# 06_NRF24L01.net
KiCad netlist of a schematic drawn in Altium Designer
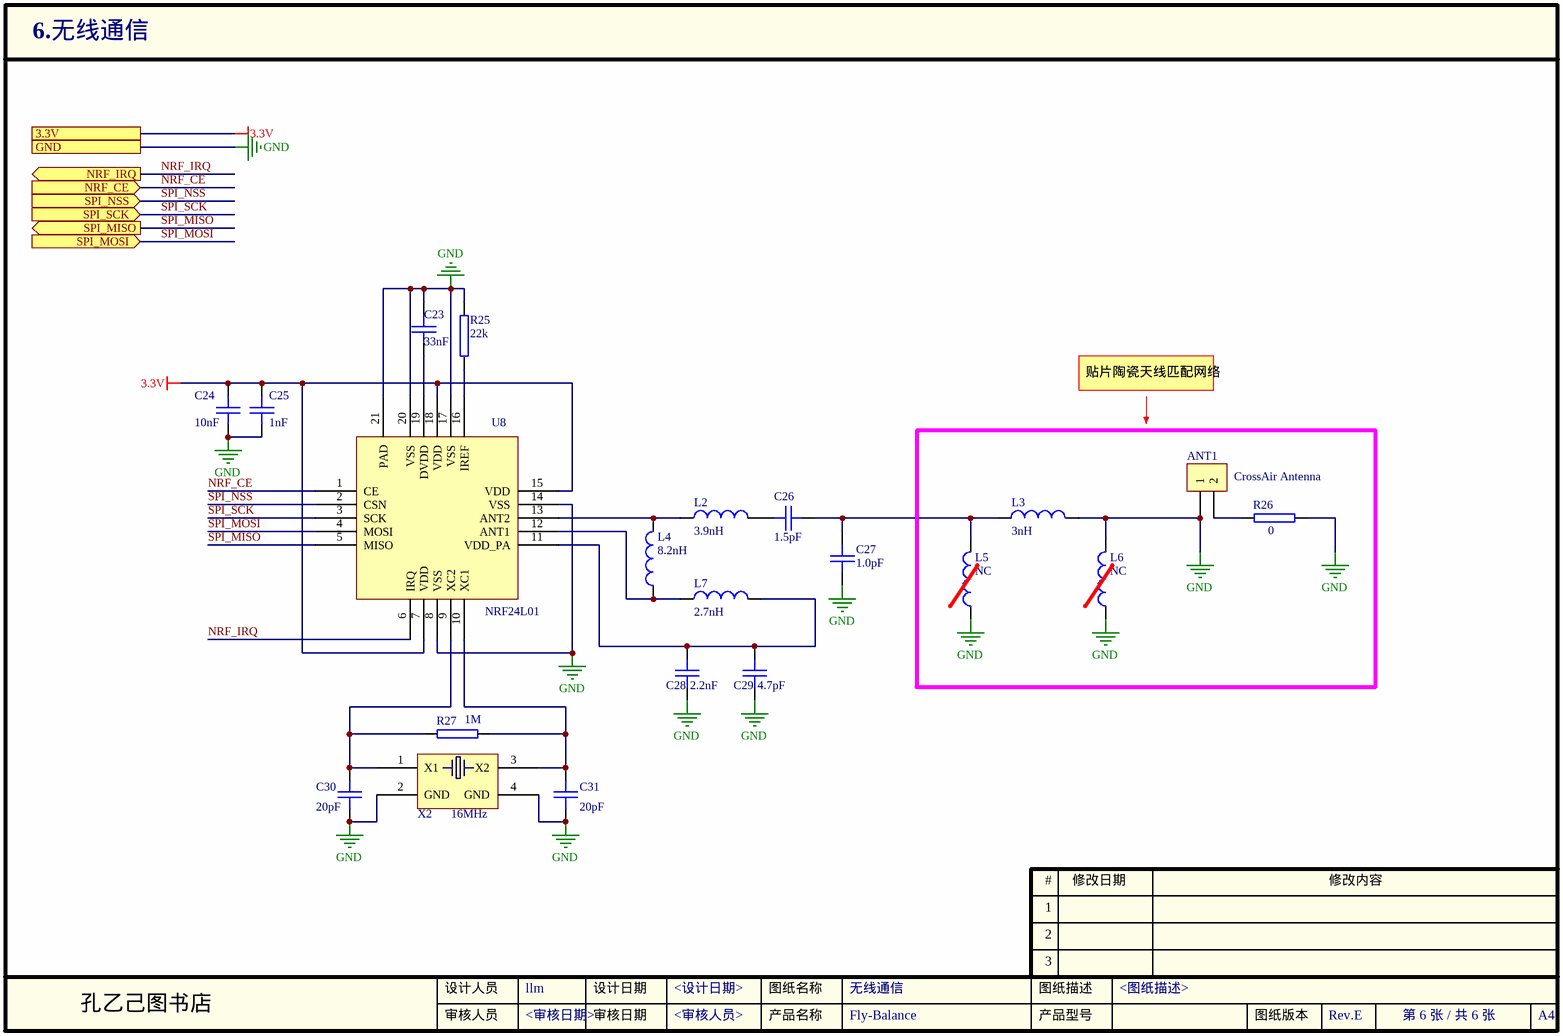
[diagram p0: 06_NRF24L01.SchDoc]

(export (version "E")
  (design (tool "Eeschema 10.0.6"))
  (components
    (comp (ref "ANT1")
      (value "CrossAir Antenna")
      (footprint "ANT-SMD_L3.1-W1.6")
      (description "Connector")
      (libsource (lib "MY_Schlib") (part "CON2"))
    )
    (comp (ref "C23")
      (value "33nF")
      (footprint "0402C")
      (description "电容")
      (libsource (lib "MY_Schlib") (part "CAP"))
    )
    (comp (ref "C24")
      (value "10nF")
      (footprint "0402C")
      (description "电容")
      (libsource (lib "MY_Schlib") (part "CAP"))
    )
    (comp (ref "C25")
      (value "1nF")
      (footprint "0402C")
      (description "电容")
      (libsource (lib "MY_Schlib") (part "CAP"))
    )
    (comp (ref "C26")
      (value "1.5pF")
      (footprint "0402C")
      (description "电容")
      (libsource (lib "MY_Schlib") (part "CAP"))
    )
    (comp (ref "C27")
      (value "1.0pF")
      (footprint "0402C")
      (description "电容")
      (libsource (lib "MY_Schlib") (part "CAP"))
    )
    (comp (ref "C28")
      (value "2.2nF")
      (footprint "0402C")
      (description "电容")
      (libsource (lib "MY_Schlib") (part "CAP"))
    )
    (comp (ref "C29")
      (value "4.7pF")
      (footprint "0402C")
      (description "电容")
      (libsource (lib "MY_Schlib") (part "CAP"))
    )
    (comp (ref "C30")
      (value "20pF")
      (footprint "0402C")
      (description "电容")
      (libsource (lib "MY_Schlib") (part "CAP"))
    )
    (comp (ref "C31")
      (value "20pF")
      (footprint "0402C")
      (description "电容")
      (libsource (lib "MY_Schlib") (part "CAP"))
    )
    (comp (ref "L2")
      (value "3.9nH")
      (footprint "0402R")
      (description "电感")
      (libsource (lib "") (part "INDUCTOR_1_1"))
    )
    (comp (ref "L3")
      (value "3nH")
      (footprint "0402R")
      (description "电感")
      (libsource (lib "") (part "INDUCTOR_1_1"))
    )
    (comp (ref "L4")
      (value "8.2nH")
      (footprint "0402R")
      (description "电感")
      (libsource (lib "MY_Schlib") (part "INDUCTOR_1"))
    )
    (comp (ref "L5")
      (value "NC")
      (footprint "0402R")
      (description "电感")
      (libsource (lib "MY_Schlib") (part "INDUCTOR_1"))
    )
    (comp (ref "L6")
      (value "NC")
      (footprint "0402R")
      (description "电感")
      (libsource (lib "MY_Schlib") (part "INDUCTOR_1"))
    )
    (comp (ref "L7")
      (value "2.7nH")
      (footprint "0402R")
      (description "电感")
      (libsource (lib "") (part "INDUCTOR_1_1"))
    )
    (comp (ref "R25")
      (value "22k")
      (footprint "0402R")
      (description "电阻")
      (libsource (lib "MY_Schlib") (part "RES"))
    )
    (comp (ref "R26")
      (value "0")
      (footprint "0402R")
      (description "电阻")
      (libsource (lib "MY_Schlib") (part "RES"))
    )
    (comp (ref "R27")
      (value "1M")
      (footprint "0402R")
      (description "电阻")
      (libsource (lib "MY_Schlib") (part "RES"))
    )
    (comp (ref "U8")
      (value "NRF24L01")
      (footprint "QFN-20_L4.0-W4.0-P0.50-BL-EP")
      (description "2.4G无线通信芯片")
      (libsource (lib "MY_Schlib") (part "NRF24L01"))
    )
    (comp (ref "X2")
      (value "16MHz")
      (footprint "OSCCC250X320X80-4N")
      (description "4pin贴片无源晶振")
      (libsource (lib "MY_Schlib") (part "XTAL4"))
    )
  )
  (nets
    (net (code "1") (name "/NRF_CE") (class "Default")
      (node (ref "U8") (pin "1") (pinfunction "CE_1") (pintype "passive"))
    )
    (net (code "2") (name "/NRF_IRQ") (class "Default")
      (node (ref "U8") (pin "6") (pinfunction "IRQ_6") (pintype "passive"))
    )
    (net (code "3") (name "/SPI_MISO") (class "Default")
      (node (ref "U8") (pin "5") (pinfunction "MISO_5") (pintype "passive"))
    )
    (net (code "4") (name "/SPI_MOSI") (class "Default")
      (node (ref "U8") (pin "4") (pinfunction "MOSI_4") (pintype "passive"))
    )
    (net (code "5") (name "/SPI_NSS") (class "Default")
      (node (ref "U8") (pin "2") (pinfunction "CSN_2") (pintype "passive"))
    )
    (net (code "6") (name "/SPI_SCK") (class "Default")
      (node (ref "U8") (pin "3") (pinfunction "SCK_3") (pintype "passive"))
    )
    (net (code "7") (name "3.3V") (class "Default")
      (node (ref "C24") (pin "1") (pinfunction "1_1") (pintype "passive"))
      (node (ref "C25") (pin "1") (pinfunction "1_1") (pintype "passive"))
      (node (ref "U8") (pin "15") (pinfunction "VDD_15") (pintype "passive"))
      (node (ref "U8") (pin "18") (pinfunction "VDD_18") (pintype "passive"))
      (node (ref "U8") (pin "7") (pinfunction "VDD_7") (pintype "passive"))
    )
    (net (code "8") (name "GND") (class "Default")
      (node (ref "ANT1") (pin "1") (pinfunction "1_1") (pintype "passive"))
      (node (ref "C23") (pin "1") (pinfunction "1_1") (pintype "passive"))
      (node (ref "C24") (pin "2") (pinfunction "2_2") (pintype "passive"))
      (node (ref "C25") (pin "2") (pinfunction "2_2") (pintype "passive"))
      (node (ref "C27") (pin "1") (pinfunction "1_1") (pintype "passive"))
      (node (ref "C28") (pin "2") (pinfunction "2_2") (pintype "passive"))
      (node (ref "C29") (pin "2") (pinfunction "2_2") (pintype "passive"))
      (node (ref "C30") (pin "1") (pinfunction "1_1") (pintype "passive"))
      (node (ref "C31") (pin "1") (pinfunction "1_1") (pintype "passive"))
      (node (ref "L3") (pin "2") (pinfunction "2_2") (pintype "passive"))
      (node (ref "L5") (pin "1") (pinfunction "1_1") (pintype "passive"))
      (node (ref "L6") (pin "1") (pinfunction "1_1") (pintype "passive"))
      (node (ref "L6") (pin "2") (pinfunction "2_2") (pintype "passive"))
      (node (ref "R25") (pin "1") (pinfunction "1_1") (pintype "passive"))
      (node (ref "R26") (pin "2") (pinfunction "2_2") (pintype "passive"))
      (node (ref "U8") (pin "14") (pinfunction "VSS_14") (pintype "passive"))
      (node (ref "U8") (pin "17") (pinfunction "VSS_17") (pintype "passive"))
      (node (ref "U8") (pin "20") (pinfunction "VSS_20") (pintype "passive"))
      (node (ref "U8") (pin "21") (pinfunction "PAD_21") (pintype "passive"))
      (node (ref "U8") (pin "8") (pinfunction "VSS_8") (pintype "passive"))
      (node (ref "X2") (pin "2") (pinfunction "GND_2") (pintype "passive"))
      (node (ref "X2") (pin "4") (pinfunction "GND_4") (pintype "passive"))
    )
    (net (code "9") (name "Net-(ANT1-Pad2)") (class "Default")
      (node (ref "ANT1") (pin "2") (pinfunction "2_2") (pintype "passive"))
      (node (ref "R26") (pin "1") (pinfunction "1_1") (pintype "passive"))
    )
    (net (code "10") (name "Net-(C26-Pad1)") (class "Default")
      (node (ref "C26") (pin "1") (pinfunction "1_1") (pintype "passive"))
      (node (ref "L2") (pin "2") (pinfunction "2_2") (pintype "passive"))
    )
    (net (code "11") (name "Net-(C26-Pad2)") (class "Default")
      (node (ref "C26") (pin "2") (pinfunction "2_2") (pintype "passive"))
      (node (ref "C27") (pin "2") (pinfunction "2_2") (pintype "passive"))
      (node (ref "L3") (pin "1") (pinfunction "1_1") (pintype "passive"))
      (node (ref "L5") (pin "2") (pinfunction "2_2") (pintype "passive"))
    )
    (net (code "12") (name "Net-(U8-ANT1)") (class "Default")
      (node (ref "L4") (pin "1") (pinfunction "1_1") (pintype "passive"))
      (node (ref "L7") (pin "1") (pinfunction "1_1") (pintype "passive"))
      (node (ref "U8") (pin "12") (pinfunction "ANT1_12") (pintype "passive"))
    )
    (net (code "13") (name "Net-(U8-ANT2)") (class "Default")
      (node (ref "L2") (pin "1") (pinfunction "1_1") (pintype "passive"))
      (node (ref "L4") (pin "2") (pinfunction "2_2") (pintype "passive"))
      (node (ref "U8") (pin "13") (pinfunction "ANT2_13") (pintype "passive"))
    )
    (net (code "14") (name "Net-(U8-DVDD)") (class "Default")
      (node (ref "C23") (pin "2") (pinfunction "2_2") (pintype "passive"))
      (node (ref "U8") (pin "19") (pinfunction "DVDD_19") (pintype "passive"))
    )
    (net (code "15") (name "Net-(U8-IREF)") (class "Default")
      (node (ref "R25") (pin "2") (pinfunction "2_2") (pintype "passive"))
      (node (ref "U8") (pin "16") (pinfunction "IREF_16") (pintype "passive"))
    )
    (net (code "16") (name "Net-(U8-VDD_PA)") (class "Default")
      (node (ref "C28") (pin "1") (pinfunction "1_1") (pintype "passive"))
      (node (ref "C29") (pin "1") (pinfunction "1_1") (pintype "passive"))
      (node (ref "L7") (pin "2") (pinfunction "2_2") (pintype "passive"))
      (node (ref "U8") (pin "11") (pinfunction "VDD_PA_11") (pintype "passive"))
    )
    (net (code "17") (name "Net-(U8-XC1)") (class "Default")
      (node (ref "C31") (pin "2") (pinfunction "2_2") (pintype "passive"))
      (node (ref "R27") (pin "2") (pinfunction "2_2") (pintype "passive"))
      (node (ref "U8") (pin "10") (pinfunction "XC1_10") (pintype "passive"))
      (node (ref "X2") (pin "3") (pinfunction "X2_3") (pintype "passive"))
    )
    (net (code "18") (name "Net-(U8-XC2)") (class "Default")
      (node (ref "C30") (pin "2") (pinfunction "2_2") (pintype "passive"))
      (node (ref "R27") (pin "1") (pinfunction "1_1") (pintype "passive"))
      (node (ref "U8") (pin "9") (pinfunction "XC2_9") (pintype "passive"))
      (node (ref "X2") (pin "1") (pinfunction "X1_1") (pintype "passive"))
    )
  )
)
